# CPU.net
KiCad netlist of a schematic drawn in Altium Designer
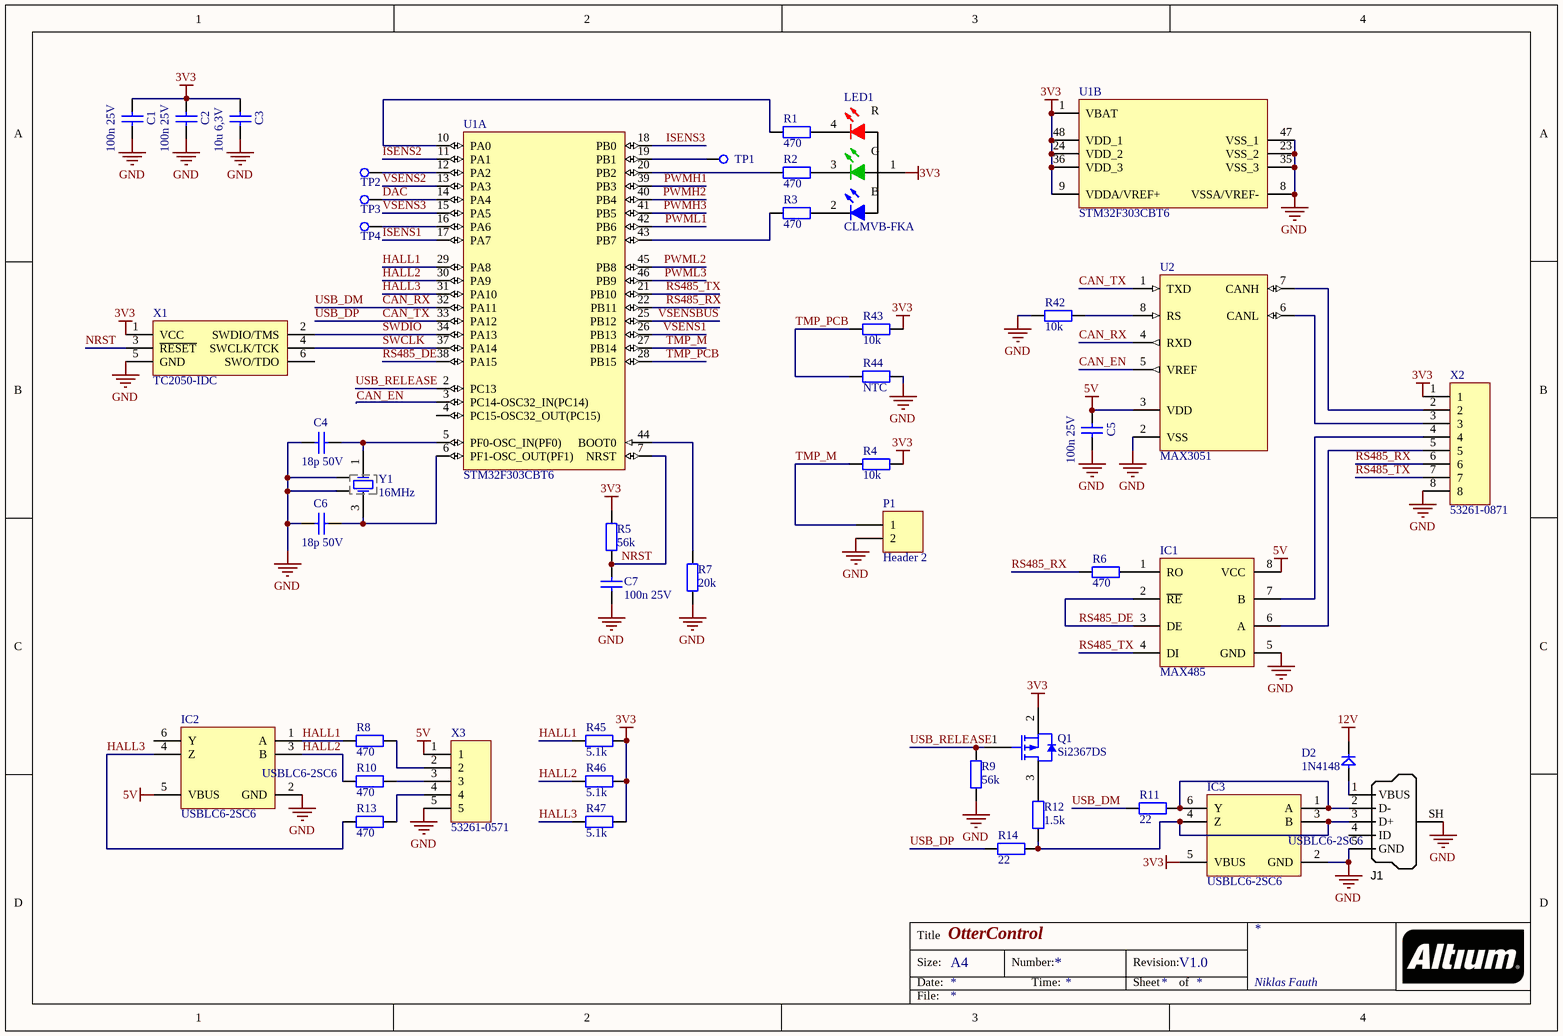
[diagram p0: CPU.SchDoc]

(export (version "E")
  (design (tool "Eeschema 10.0.6"))
  (components
    (comp (ref "C1")
      (value "100n 25V")
      (footprint "C-0603-H")
      (description "Capacitor 100n 25V")
      (libsource (lib "Passives") (part "C-0603-100n-25V"))
    )
    (comp (ref "C2")
      (value "100n 25V")
      (footprint "C-0603-H")
      (description "Capacitor 100n 25V")
      (libsource (lib "Passives") (part "C-0603-100n-25V"))
    )
    (comp (ref "C3")
      (value "10u 6,3V")
      (footprint "C-0603-H")
      (description "Capacitor 10uF 6,3V")
      (libsource (lib "Passives") (part "C-0603-10u-6,3V"))
    )
    (comp (ref "C4")
      (value "18p 50V")
      (footprint "C-0603-H")
      (description "Capacitor 18p 50V")
      (libsource (lib "Passives") (part "C-0402-18p-50V"))
    )
    (comp (ref "C5")
      (value "100n 25V")
      (footprint "C-0603-H")
      (description "Capacitor 100n 25V")
      (libsource (lib "Passives") (part "C-0603-100n-25V"))
    )
    (comp (ref "C6")
      (value "18p 50V")
      (footprint "C-0603-H")
      (description "Capacitor 18p 50V")
      (libsource (lib "Passives") (part "C-0402-18p-50V"))
    )
    (comp (ref "C7")
      (value "100n 25V")
      (footprint "C-0603-H")
      (description "Capacitor 100n 25V")
      (libsource (lib "Passives") (part "C-0603-100n-25V"))
    )
    (comp (ref "D2")
      (value "1N4148")
      (footprint "SOD323F")
      (description "Diode 1N4148")
      (libsource (lib "advanced") (part "1N4148"))
    )
    (comp (ref "IC1")
      (value "MAX485")
      (footprint "SOIC-8")
      (description "RS485 transceiver")
      (libsource (lib "advanced") (part "MAX485"))
    )
    (comp (ref "IC2")
      (value "USBLC6-2SC6")
      (footprint "SOT23-6")
      (description "USB protection")
      (libsource (lib "gpn-badge") (part "USBLC6-2SC6"))
    )
    (comp (ref "IC3")
      (value "USBLC6-2SC6")
      (footprint "SOT23-6")
      (description "USB protection")
      (libsource (lib "gpn-badge") (part "USBLC6-2SC6"))
    )
    (comp (ref "J1")
      (value "USB Micro Type B (recommended if hand soldering)")
      (footprint "USB_Micro-Molex")
      (description "Connector SMD-THD USB Micro Type B middle mount")
      (libsource (lib "gpn-badge") (part "USB_Micro_MOLEX"))
    )
    (comp (ref "LED1")
      (value "CLMVB-FKA")
      (footprint "uLED")
      (description "CLMVB-FKA RGB")
      (libsource (lib "advanced") (part "uLED-RGB"))
    )
    (comp (ref "P1")
      (value "Header 2")
      (footprint "HDR1X2")
      (description "Header, 2-Pin")
      (fields (field (name "PUBLISHER") "Altium Limited"))
      (libsource (lib "Miscellaneous Connectors") (part "Header 2"))
    )
    (comp (ref "Q1") (value "Si2367DS") (footprint "SOT-23") (libsource (lib "advanced") (part "MOSFET-P")))
    (comp (ref "R1")
      (value "470")
      (footprint "R-0603-H")
      (description "Resistor 470")
      (libsource (lib "") (part "R-0402-470_1"))
    )
    (comp (ref "R2")
      (value "470")
      (footprint "R-0603-H")
      (description "Resistor 470")
      (libsource (lib "") (part "R-0402-470_1"))
    )
    (comp (ref "R3")
      (value "470")
      (footprint "R-0603-H")
      (description "Resistor 470")
      (libsource (lib "") (part "R-0402-470_1"))
    )
    (comp (ref "R4")
      (value "10k")
      (footprint "R-0603-H")
      (description "Resistor 10k")
      (libsource (lib "Passives") (part "R-0603-10k"))
    )
    (comp (ref "R5")
      (value "56k")
      (footprint "R-0603-H")
      (description "Resistor 4k7")
      (libsource (lib "Passives") (part "R-0603-47k"))
    )
    (comp (ref "R6")
      (value "470")
      (footprint "R-0603-H")
      (description "Resistor 470")
      (libsource (lib "Passives") (part "R-0402-470"))
    )
    (comp (ref "R7")
      (value "20k")
      (footprint "R-0603-H")
      (description "Resistor 20k")
      (libsource (lib "Passives") (part "R-0603-20k"))
    )
    (comp (ref "R8")
      (value "470")
      (footprint "R-0603-H")
      (description "Resistor 470")
      (libsource (lib "Passives") (part "R-0402-470"))
    )
    (comp (ref "R9")
      (value "56k")
      (footprint "R-0603-H")
      (description "Resistor 4k7")
      (libsource (lib "") (part "R-0603-47k_1"))
    )
    (comp (ref "R10")
      (value "470")
      (footprint "R-0603-H")
      (description "Resistor 470")
      (libsource (lib "Passives") (part "R-0402-470"))
    )
    (comp (ref "R11")
      (value "22")
      (footprint "R-0603-H")
      (description "Resistor 22")
      (libsource (lib "Passives") (part "R-0603-22"))
    )
    (comp (ref "R12")
      (value "1.5k")
      (footprint "R-0603-H")
      (description "Resistor 1.5k")
      (libsource (lib "Passives") (part "R-0603-1k5"))
    )
    (comp (ref "R13")
      (value "470")
      (footprint "R-0603-H")
      (description "Resistor 470")
      (libsource (lib "Passives") (part "R-0402-470"))
    )
    (comp (ref "R14")
      (value "22")
      (footprint "R-0603-H")
      (description "Resistor 22")
      (libsource (lib "Passives") (part "R-0603-22"))
    )
    (comp (ref "R42")
      (value "10k")
      (footprint "R-0603-H")
      (description "Resistor 10k")
      (libsource (lib "Passives") (part "R-0603-10k"))
    )
    (comp (ref "R43")
      (value "10k")
      (footprint "R-0603-H")
      (description "Resistor 10k")
      (libsource (lib "Passives") (part "R-0603-10k"))
    )
    (comp (ref "R44")
      (value "NTC")
      (footprint "R-0603-H")
      (description "Resistor 10k")
      (libsource (lib "Passives") (part "R-0603-10k"))
    )
    (comp (ref "R45")
      (value "5.1k")
      (footprint "R-0603-H")
      (description "Resistor 5.1k")
      (libsource (lib "Passives") (part "R-0603-5k1"))
    )
    (comp (ref "R46")
      (value "5.1k")
      (footprint "R-0603-H")
      (description "Resistor 5.1k")
      (libsource (lib "Passives") (part "R-0603-5k1"))
    )
    (comp (ref "R47")
      (value "5.1k")
      (footprint "R-0603-H")
      (description "Resistor 5.1k")
      (libsource (lib "Passives") (part "R-0603-5k1"))
    )
    (comp (ref "TP1") (value "TP-SMD") (footprint "TP") (libsource (lib "advanced") (part "TP-SMD")))
    (comp (ref "TP2") (value "TP-SMD") (footprint "TP") (libsource (lib "advanced") (part "TP-SMD")))
    (comp (ref "TP3") (value "TP-SMD") (footprint "TP") (libsource (lib "advanced") (part "TP-SMD")))
    (comp (ref "TP4") (value "TP-SMD") (footprint "TP") (libsource (lib "advanced") (part "TP-SMD")))
    (comp (ref "U1")
      (value "STM32F303CBT6")
      (footprint "STM-LQFP48_N")
      (libsource (lib "Altium Content Vault") (part "MC-ARM-STM32F303-SQ48"))
    )
    (comp (ref "U2")
      (value "MAX3051")
      (footprint "SOIC-SN8_N")
      (description "High-Speed CAN Transceiver, 8-Pin SOIC, Industrial Temperature")
      (libsource (lib "Altium Content Vault") (part "COM-TRX-MCP2551-8"))
    )
    (comp (ref "X1")
      (value "TC2050-IDC")
      (footprint "TC2030-IDC-NL")
      (description "TC2050-IDC SWD")
      (libsource (lib "advanced") (part "TAG-Connect-SWD"))
    )
    (comp (ref "X2")
      (value "53261-0871")
      (footprint "mlx-picoBlade-8p-right-SMD")
      (libsource (lib "advanced") (part "MLX-picoBlade-8P-right-SMD"))
    )
    (comp (ref "X3")
      (value "53261-0571")
      (footprint "mlx-picoBlade-5p-right-SMD")
      (libsource (lib "advanced") (part "MLX-picoBlade-5P-right-SMD"))
    )
    (comp (ref "Y1") (value "16MHz") (footprint "ABM10") (libsource (lib "advanced") (part "ABM10-16MHz")))
  )
  (nets
    (net (code "1") (name "/CAN_EN") (class "Default")
      (node (ref "U1") (pin "3") (pinfunction "PC14-OSC32_IN(PC14)_3") (pintype "bidirectional"))
      (node (ref "U2") (pin "5") (pinfunction "VREF_5") (pintype "output"))
    )
    (net (code "2") (name "/CAN_RX") (class "Default")
      (node (ref "R11") (pin "2") (pinfunction "2_2") (pintype "passive"))
      (node (ref "U1") (pin "32") (pinfunction "PA11_32") (pintype "bidirectional"))
      (node (ref "U2") (pin "4") (pinfunction "RXD_4") (pintype "output"))
    )
    (net (code "3") (name "/CAN_TX") (class "Default")
      (node (ref "R14") (pin "2") (pinfunction "2_2") (pintype "passive"))
      (node (ref "U1") (pin "33") (pinfunction "PA12_33") (pintype "bidirectional"))
      (node (ref "U2") (pin "1") (pinfunction "TXD_1") (pintype "input"))
    )
    (net (code "4") (name "/DAC") (class "Default")
      (node (ref "TP3") (pin "1") (pintype "passive"))
      (node (ref "U1") (pin "14") (pinfunction "PA4_14") (pintype "bidirectional"))
    )
    (net (code "5") (name "/HALL1") (class "Default")
      (node (ref "IC2") (pin "1") (pinfunction "A_1") (pintype "passive"))
      (node (ref "R45") (pin "1") (pinfunction "1_1") (pintype "passive"))
      (node (ref "R8") (pin "1") (pinfunction "1_1") (pintype "passive"))
      (node (ref "U1") (pin "29") (pinfunction "PA8_29") (pintype "bidirectional"))
    )
    (net (code "6") (name "/HALL2") (class "Default")
      (node (ref "IC2") (pin "3") (pinfunction "B_3") (pintype "passive"))
      (node (ref "R10") (pin "1") (pinfunction "1_1") (pintype "passive"))
      (node (ref "R46") (pin "1") (pinfunction "1_1") (pintype "passive"))
      (node (ref "U1") (pin "30") (pinfunction "PA9_30") (pintype "bidirectional"))
    )
    (net (code "7") (name "/HALL3") (class "Default")
      (node (ref "IC2") (pin "4") (pinfunction "Z_4") (pintype "passive"))
      (node (ref "R13") (pin "1") (pinfunction "1_1") (pintype "passive"))
      (node (ref "R47") (pin "1") (pinfunction "1_1") (pintype "passive"))
      (node (ref "U1") (pin "31") (pinfunction "PA10_31") (pintype "bidirectional"))
    )
    (net (code "8") (name "/ISENS1") (class "Default")
      (node (ref "U1") (pin "17") (pinfunction "PA7_17") (pintype "bidirectional"))
    )
    (net (code "9") (name "/ISENS2") (class "Default")
      (node (ref "U1") (pin "11") (pinfunction "PA1_11") (pintype "bidirectional"))
    )
    (net (code "10") (name "/ISENS3") (class "Default")
      (node (ref "U1") (pin "18") (pinfunction "PB0_18") (pintype "bidirectional"))
    )
    (net (code "11") (name "/NRST") (class "Default")
      (node (ref "C7") (pin "2") (pinfunction "2_2") (pintype "passive"))
      (node (ref "R5") (pin "1") (pinfunction "1_1") (pintype "passive"))
      (node (ref "U1") (pin "7") (pinfunction "NRST_7") (pintype "bidirectional"))
      (node (ref "X1") (pin "3") (pinfunction "~{RESET}_3") (pintype "passive"))
    )
    (net (code "12") (name "/PWMH1") (class "Default")
      (node (ref "U1") (pin "39") (pinfunction "PB3_39") (pintype "bidirectional"))
    )
    (net (code "13") (name "/PWMH2") (class "Default")
      (node (ref "U1") (pin "40") (pinfunction "PB4_40") (pintype "bidirectional"))
    )
    (net (code "14") (name "/PWMH3") (class "Default")
      (node (ref "U1") (pin "41") (pinfunction "PB5_41") (pintype "bidirectional"))
    )
    (net (code "15") (name "/PWML1") (class "Default")
      (node (ref "U1") (pin "42") (pinfunction "PB6_42") (pintype "bidirectional"))
    )
    (net (code "16") (name "/PWML2") (class "Default")
      (node (ref "U1") (pin "45") (pinfunction "PB8_45") (pintype "bidirectional"))
    )
    (net (code "17") (name "/PWML3") (class "Default")
      (node (ref "U1") (pin "46") (pinfunction "PB9_46") (pintype "bidirectional"))
    )
    (net (code "18") (name "/RS485_DE") (class "Default")
      (node (ref "IC1") (pin "2") (pinfunction "~{RE}_2") (pintype "passive"))
      (node (ref "IC1") (pin "3") (pinfunction "DE_3") (pintype "passive"))
      (node (ref "U1") (pin "38") (pinfunction "PA15_38") (pintype "bidirectional"))
    )
    (net (code "19") (name "/RS485_RX") (class "Default")
      (node (ref "R6") (pin "1") (pinfunction "1_1") (pintype "passive"))
      (node (ref "U1") (pin "22") (pinfunction "PB11_22") (pintype "bidirectional"))
      (node (ref "X2") (pin "6") (pinfunction "6_6") (pintype "power_in"))
    )
    (net (code "20") (name "/RS485_TX") (class "Default")
      (node (ref "IC1") (pin "4") (pinfunction "DI_4") (pintype "passive"))
      (node (ref "U1") (pin "21") (pinfunction "PB10_21") (pintype "bidirectional"))
      (node (ref "X2") (pin "7") (pinfunction "7_7") (pintype "power_in"))
    )
    (net (code "21") (name "/SWCLK") (class "Default")
      (node (ref "U1") (pin "37") (pinfunction "PA14_37") (pintype "bidirectional"))
      (node (ref "X1") (pin "4") (pinfunction "SWCLK/TCK_4") (pintype "passive"))
    )
    (net (code "22") (name "/SWDIO") (class "Default")
      (node (ref "U1") (pin "34") (pinfunction "PA13_34") (pintype "bidirectional"))
      (node (ref "X1") (pin "2") (pinfunction "SWDIO/TMS_2") (pintype "passive"))
    )
    (net (code "23") (name "/TMP_M") (class "Default")
      (node (ref "P1") (pin "1") (pinfunction "1_1") (pintype "passive"))
      (node (ref "R4") (pin "1") (pinfunction "1_1") (pintype "passive"))
      (node (ref "U1") (pin "27") (pinfunction "PB14_27") (pintype "bidirectional"))
    )
    (net (code "24") (name "/TMP_PCB") (class "Default")
      (node (ref "R43") (pin "1") (pinfunction "1_1") (pintype "passive"))
      (node (ref "R44") (pin "1") (pinfunction "1_1") (pintype "passive"))
      (node (ref "U1") (pin "28") (pinfunction "PB15_28") (pintype "bidirectional"))
    )
    (net (code "25") (name "/USB_RELEASE") (class "Default")
      (node (ref "Q1") (pin "1") (pintype "passive"))
      (node (ref "R9") (pin "1") (pinfunction "1_1") (pintype "passive"))
      (node (ref "U1") (pin "2") (pinfunction "PC13_2") (pintype "bidirectional"))
    )
    (net (code "26") (name "/VSENS1") (class "Default")
      (node (ref "U1") (pin "26") (pinfunction "PB13_26") (pintype "bidirectional"))
    )
    (net (code "27") (name "/VSENS2") (class "Default")
      (node (ref "U1") (pin "13") (pinfunction "PA3_13") (pintype "bidirectional"))
    )
    (net (code "28") (name "/VSENS3") (class "Default")
      (node (ref "U1") (pin "15") (pinfunction "PA5_15") (pintype "bidirectional"))
    )
    (net (code "29") (name "/VSENSBUS") (class "Default")
      (node (ref "U1") (pin "25") (pinfunction "PB12_25") (pintype "bidirectional"))
    )
    (net (code "30") (name "3V3") (class "Default")
      (node (ref "C1") (pin "2") (pinfunction "2_2") (pintype "passive"))
      (node (ref "C2") (pin "2") (pinfunction "2_2") (pintype "passive"))
      (node (ref "C3") (pin "2") (pinfunction "2_2") (pintype "passive"))
      (node (ref "IC3") (pin "5") (pinfunction "VBUS_5") (pintype "passive"))
      (node (ref "LED1") (pin "1") (pinfunction "A2_1") (pintype "passive"))
      (node (ref "Q1") (pin "2") (pintype "passive"))
      (node (ref "R4") (pin "2") (pinfunction "2_2") (pintype "passive"))
      (node (ref "R43") (pin "2") (pinfunction "2_2") (pintype "passive"))
      (node (ref "R45") (pin "2") (pinfunction "2_2") (pintype "passive"))
      (node (ref "R46") (pin "2") (pinfunction "2_2") (pintype "passive"))
      (node (ref "R47") (pin "2") (pinfunction "2_2") (pintype "passive"))
      (node (ref "R5") (pin "2") (pinfunction "2_2") (pintype "passive"))
      (node (ref "U1") (pin "1") (pinfunction "VBAT_1") (pintype "power_in"))
      (node (ref "U1") (pin "24") (pinfunction "VDD_2_24") (pintype "power_in"))
      (node (ref "U1") (pin "36") (pinfunction "VDD_3_36") (pintype "power_in"))
      (node (ref "U1") (pin "48") (pinfunction "VDD_1_48") (pintype "power_in"))
      (node (ref "U1") (pin "9") (pinfunction "VDDA/VREF+_9") (pintype "power_in"))
      (node (ref "X1") (pin "1") (pinfunction "VCC_1") (pintype "passive"))
      (node (ref "X2") (pin "1") (pinfunction "1_1") (pintype "passive"))
    )
    (net (code "31") (name "5V") (class "Default")
      (node (ref "C5") (pin "2") (pinfunction "2_2") (pintype "passive"))
      (node (ref "IC1") (pin "8") (pinfunction "VCC_8") (pintype "passive"))
      (node (ref "IC2") (pin "5") (pinfunction "VBUS_5") (pintype "passive"))
      (node (ref "U2") (pin "3") (pinfunction "VDD_3") (pintype "power_in"))
      (node (ref "X3") (pin "1") (pinfunction "1_1") (pintype "passive"))
    )
    (net (code "32") (name "12V") (class "Default")
      (node (ref "D2") (pin "2") (pinfunction "kt_2") (pintype "passive"))
    )
    (net (code "33") (name "GND") (class "Default")
      (node (ref "C1") (pin "1") (pinfunction "1_1") (pintype "passive"))
      (node (ref "C2") (pin "1") (pinfunction "1_1") (pintype "passive"))
      (node (ref "C3") (pin "1") (pinfunction "1_1") (pintype "passive"))
      (node (ref "C4") (pin "2") (pinfunction "2_2") (pintype "passive"))
      (node (ref "C5") (pin "1") (pinfunction "1_1") (pintype "passive"))
      (node (ref "C6") (pin "2") (pinfunction "2_2") (pintype "passive"))
      (node (ref "C7") (pin "1") (pinfunction "1_1") (pintype "passive"))
      (node (ref "IC1") (pin "5") (pinfunction "GND_5") (pintype "passive"))
      (node (ref "IC2") (pin "2") (pinfunction "GND_2") (pintype "passive"))
      (node (ref "IC3") (pin "2") (pinfunction "GND_2") (pintype "passive"))
      (node (ref "J1") (pin "5") (pinfunction "GND_5") (pintype "passive"))
      (node (ref "J1") (pin "SH") (pinfunction "Shell_SH") (pintype "passive"))
      (node (ref "P1") (pin "2") (pinfunction "2_2") (pintype "passive"))
      (node (ref "R42") (pin "1") (pinfunction "1_1") (pintype "passive"))
      (node (ref "R44") (pin "2") (pinfunction "2_2") (pintype "passive"))
      (node (ref "R7") (pin "1") (pinfunction "1_1") (pintype "passive"))
      (node (ref "R9") (pin "2") (pinfunction "2_2") (pintype "passive"))
      (node (ref "U1") (pin "23") (pinfunction "VSS_2_23") (pintype "power_in"))
      (node (ref "U1") (pin "35") (pinfunction "VSS_3_35") (pintype "power_in"))
      (node (ref "U1") (pin "47") (pinfunction "VSS_1_47") (pintype "power_in"))
      (node (ref "U1") (pin "8") (pinfunction "VSSA/VREF-_8") (pintype "power_in"))
      (node (ref "U2") (pin "2") (pinfunction "VSS_2") (pintype "power_in"))
      (node (ref "X1") (pin "5") (pinfunction "GND_5") (pintype "passive"))
      (node (ref "X2") (pin "8") (pinfunction "8_8") (pintype "power_in"))
      (node (ref "X3") (pin "5") (pinfunction "5_5") (pintype "passive"))
      (node (ref "Y1") (pin "2") (pintype "power_in"))
      (node (ref "Y1") (pin "4") (pintype "power_in"))
    )
    (net (code "34") (name "Net-(D2-an)") (class "Default")
      (node (ref "D2") (pin "1") (pinfunction "an_1") (pintype "passive"))
      (node (ref "J1") (pin "1") (pinfunction "VBUS_1") (pintype "passive"))
    )
    (net (code "35") (name "Net-(IC1-A)") (class "Default")
      (node (ref "IC1") (pin "6") (pinfunction "A_6") (pintype "passive"))
      (node (ref "X2") (pin "5") (pinfunction "5_5") (pintype "passive"))
    )
    (net (code "36") (name "Net-(IC1-B)") (class "Default")
      (node (ref "IC1") (pin "7") (pinfunction "B_7") (pintype "passive"))
      (node (ref "X2") (pin "4") (pinfunction "4_4") (pintype "passive"))
    )
    (net (code "37") (name "Net-(IC1-RO)") (class "Default")
      (node (ref "IC1") (pin "1") (pinfunction "RO_1") (pintype "passive"))
      (node (ref "R6") (pin "2") (pinfunction "2_2") (pintype "passive"))
    )
    (net (code "38") (name "Net-(IC3-A)") (class "Default")
      (node (ref "IC3") (pin "1") (pinfunction "A_1") (pintype "passive"))
      (node (ref "IC3") (pin "6") (pinfunction "Y_6") (pintype "passive"))
      (node (ref "J1") (pin "2") (pinfunction "D-_2") (pintype "passive"))
      (node (ref "R11") (pin "1") (pinfunction "1_1") (pintype "passive"))
    )
    (net (code "39") (name "Net-(IC3-B)") (class "Default")
      (node (ref "IC3") (pin "3") (pinfunction "B_3") (pintype "passive"))
      (node (ref "IC3") (pin "4") (pinfunction "Z_4") (pintype "passive"))
      (node (ref "J1") (pin "3") (pinfunction "D+_3") (pintype "passive"))
      (node (ref "R12") (pin "1") (pinfunction "1_1") (pintype "passive"))
      (node (ref "R14") (pin "1") (pinfunction "1_1") (pintype "passive"))
    )
    (net (code "40") (name "Net-(LED1-B)") (class "Default")
      (node (ref "LED1") (pin "2") (pinfunction "B_2") (pintype "passive"))
      (node (ref "R3") (pin "1") (pinfunction "1_1") (pintype "passive"))
    )
    (net (code "41") (name "Net-(LED1-G)") (class "Default")
      (node (ref "LED1") (pin "3") (pinfunction "G_3") (pintype "passive"))
      (node (ref "R2") (pin "1") (pinfunction "1_1") (pintype "passive"))
    )
    (net (code "42") (name "Net-(LED1-R)") (class "Default")
      (node (ref "LED1") (pin "4") (pinfunction "R_4") (pintype "passive"))
      (node (ref "R1") (pin "1") (pinfunction "1_1") (pintype "passive"))
    )
    (net (code "43") (name "Net-(Q1-Pad3)") (class "Default")
      (node (ref "Q1") (pin "3") (pintype "passive"))
      (node (ref "R12") (pin "2") (pinfunction "2_2") (pintype "passive"))
    )
    (net (code "44") (name "Net-(R8-Pad2)") (class "Default")
      (node (ref "R8") (pin "2") (pinfunction "2_2") (pintype "passive"))
      (node (ref "X3") (pin "2") (pinfunction "2_2") (pintype "passive"))
    )
    (net (code "45") (name "Net-(R10-Pad2)") (class "Default")
      (node (ref "R10") (pin "2") (pinfunction "2_2") (pintype "passive"))
      (node (ref "X3") (pin "3") (pinfunction "3_3") (pintype "passive"))
    )
    (net (code "46") (name "Net-(R13-Pad2)") (class "Default")
      (node (ref "R13") (pin "2") (pinfunction "2_2") (pintype "passive"))
      (node (ref "X3") (pin "4") (pinfunction "4_4") (pintype "passive"))
    )
    (net (code "47") (name "Net-(U1A-BOOT0)") (class "Default")
      (node (ref "R7") (pin "2") (pinfunction "2_2") (pintype "passive"))
      (node (ref "U1") (pin "44") (pinfunction "BOOT0_44") (pintype "input"))
    )
    (net (code "48") (name "Net-(U1A-PA0)") (class "Default")
      (node (ref "R1") (pin "2") (pinfunction "2_2") (pintype "passive"))
      (node (ref "U1") (pin "10") (pinfunction "PA0_10") (pintype "bidirectional"))
    )
    (net (code "49") (name "Net-(U1A-PA2)") (class "Default")
      (node (ref "TP2") (pin "1") (pintype "passive"))
      (node (ref "U1") (pin "12") (pinfunction "PA2_12") (pintype "bidirectional"))
    )
    (net (code "50") (name "Net-(U1A-PA6)") (class "Default")
      (node (ref "TP4") (pin "1") (pintype "passive"))
      (node (ref "U1") (pin "16") (pinfunction "PA6_16") (pintype "bidirectional"))
    )
    (net (code "51") (name "Net-(U1A-PB1)") (class "Default")
      (node (ref "TP1") (pin "1") (pintype "passive"))
      (node (ref "U1") (pin "19") (pinfunction "PB1_19") (pintype "bidirectional"))
    )
    (net (code "52") (name "Net-(U1A-PB2)") (class "Default")
      (node (ref "R2") (pin "2") (pinfunction "2_2") (pintype "passive"))
      (node (ref "U1") (pin "20") (pinfunction "PB2_20") (pintype "bidirectional"))
    )
    (net (code "53") (name "Net-(U1A-PB7)") (class "Default")
      (node (ref "R3") (pin "2") (pinfunction "2_2") (pintype "passive"))
      (node (ref "U1") (pin "43") (pinfunction "PB7_43") (pintype "bidirectional"))
    )
    (net (code "54") (name "Net-(U1A-PF0-OSC_IN(PF0))") (class "Default")
      (node (ref "C4") (pin "1") (pinfunction "1_1") (pintype "passive"))
      (node (ref "U1") (pin "5") (pinfunction "PF0-OSC_IN(PF0)_5") (pintype "bidirectional"))
      (node (ref "Y1") (pin "1") (pintype "power_in"))
    )
    (net (code "55") (name "Net-(U1A-PF1-OSC_OUT(PF1))") (class "Default")
      (node (ref "C6") (pin "1") (pinfunction "1_1") (pintype "passive"))
      (node (ref "U1") (pin "6") (pinfunction "PF1-OSC_OUT(PF1)_6") (pintype "bidirectional"))
      (node (ref "Y1") (pin "3") (pintype "power_in"))
    )
    (net (code "56") (name "Net-(U2-CANH)") (class "Default")
      (node (ref "U2") (pin "7") (pinfunction "CANH_7") (pintype "bidirectional"))
      (node (ref "X2") (pin "2") (pinfunction "2_2") (pintype "passive"))
    )
    (net (code "57") (name "Net-(U2-CANL)") (class "Default")
      (node (ref "U2") (pin "6") (pinfunction "CANL_6") (pintype "bidirectional"))
      (node (ref "X2") (pin "3") (pinfunction "3_3") (pintype "passive"))
    )
    (net (code "58") (name "Net-(U2-RS)") (class "Default")
      (node (ref "R42") (pin "2") (pinfunction "2_2") (pintype "passive"))
      (node (ref "U2") (pin "8") (pinfunction "RS_8") (pintype "input"))
    )
    (net (code "59") (name "unconnected-(IC2-Y-Pad6)") (class "Default")
      (node (ref "IC2") (pin "6") (pinfunction "Y_6") (pintype "passive"))
    )
    (net (code "60") (name "unconnected-(J1-ID-Pad4)") (class "Default")
      (node (ref "J1") (pin "4") (pinfunction "ID_4") (pintype "passive"))
    )
    (net (code "61") (name "unconnected-(U1A-PC15-OSC32_OUT(PC15)-Pad4)") (class "Default")
      (node (ref "U1") (pin "4") (pinfunction "PC15-OSC32_OUT(PC15)_4") (pintype "bidirectional"))
    )
    (net (code "62") (name "unconnected-(X1-SWO{slash}TDO-Pad6)") (class "Default")
      (node (ref "X1") (pin "6") (pinfunction "SWO/TDO_6") (pintype "passive"))
    )
  )
)
